# liron.net
KiCad netlist of a schematic drawn in EAGLE
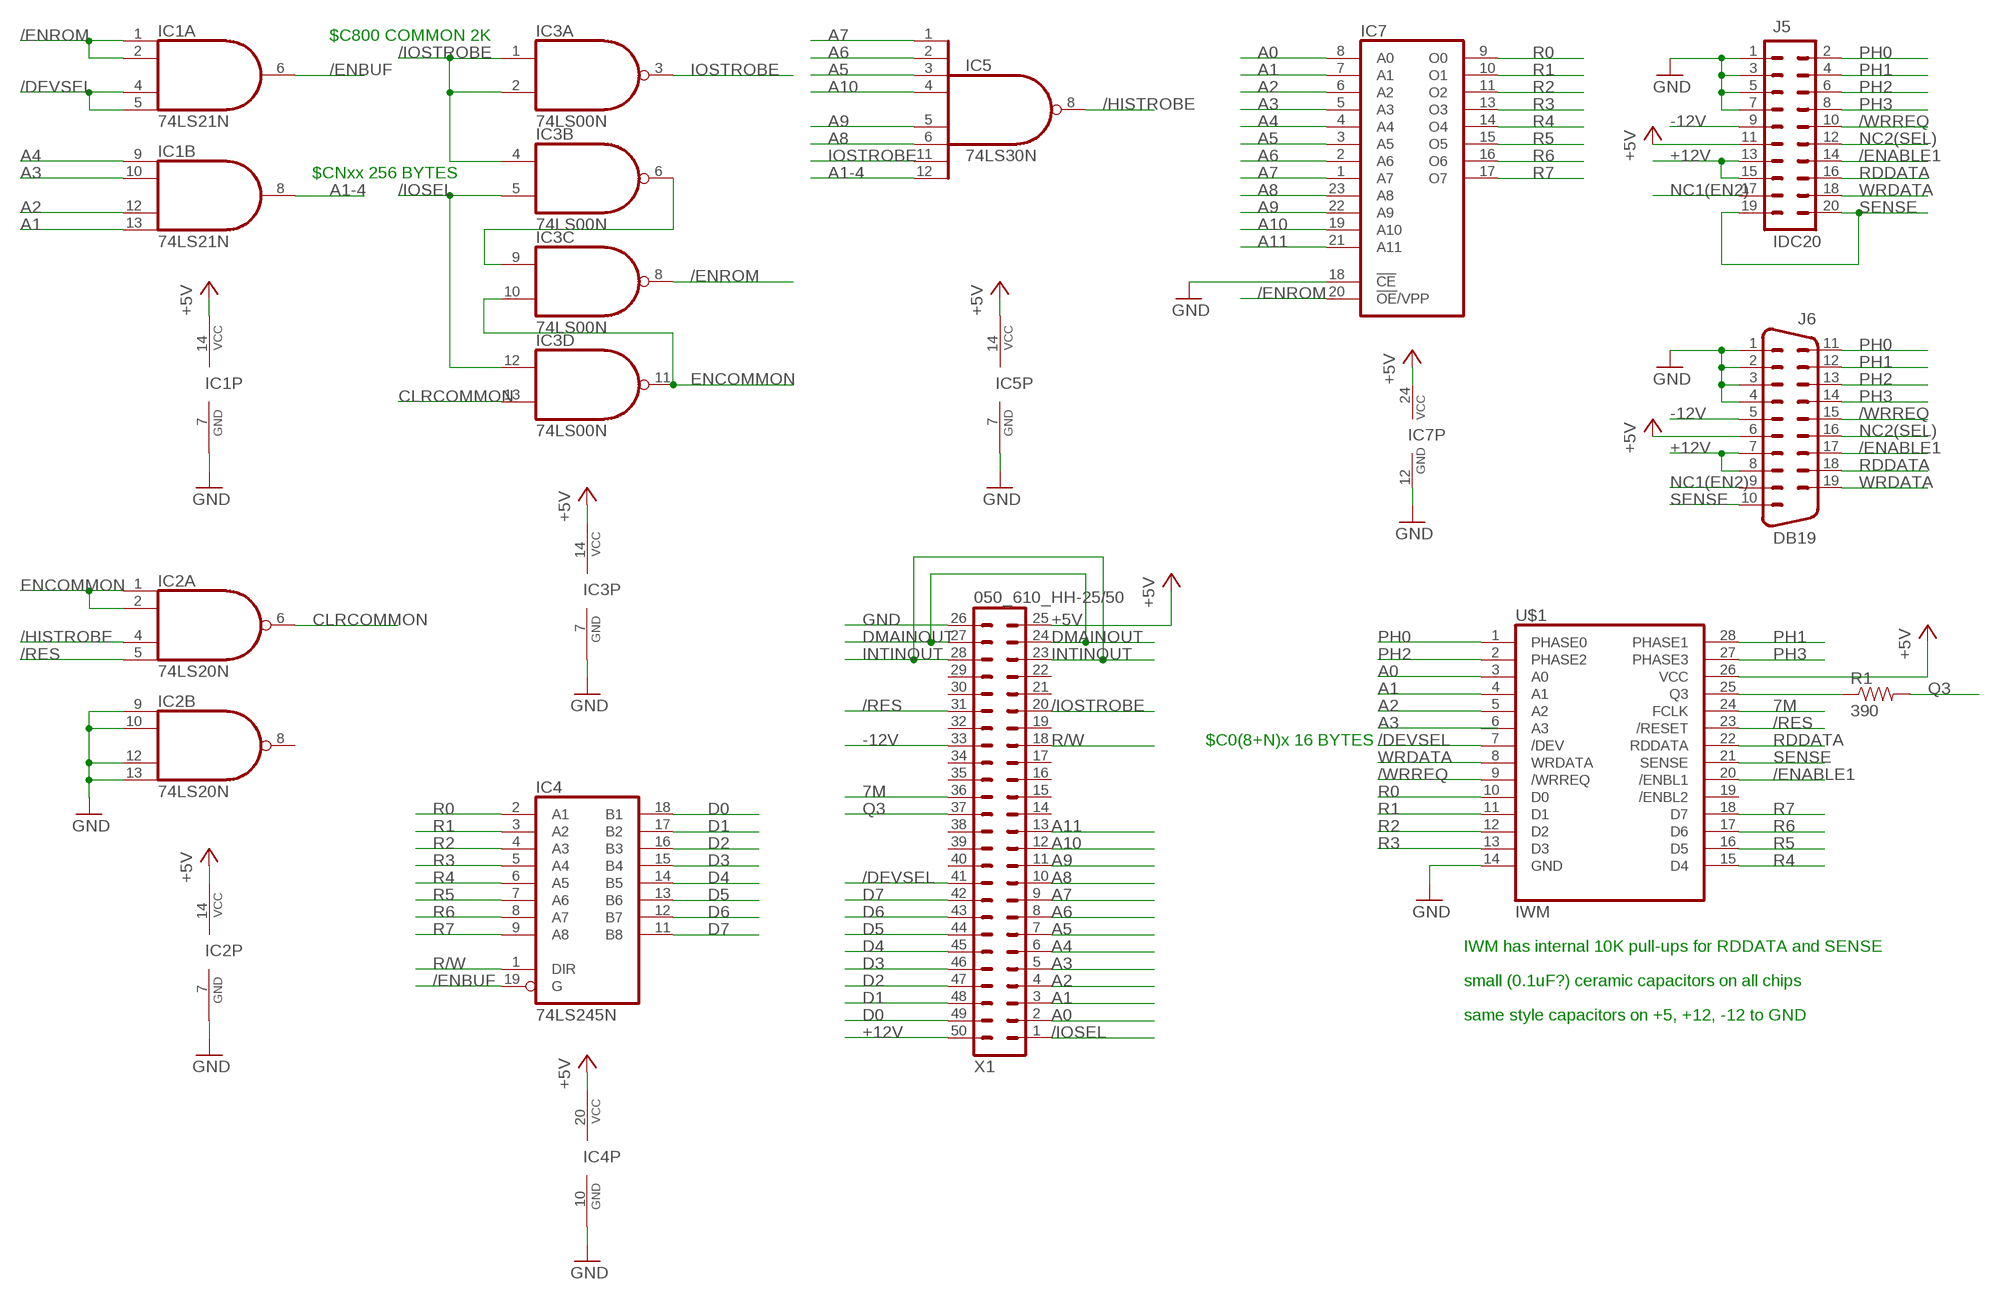
[diagram p0: schematic, sheet 1]

(export (version "E")
  (design (tool "Eeschema 10.0.6"))
  (components
    (comp (ref "IC1")
      (value "74LS21N")
      (footprint "eagle-import:DIL14")
      (libsource (lib "eagle-import") (part "7421NLS"))
    )
    (comp (ref "IC2")
      (value "74LS20N")
      (footprint "eagle-import:DIL14")
      (libsource (lib "eagle-import") (part "7420NLS"))
    )
    (comp (ref "IC3")
      (value "74LS00N")
      (footprint "eagle-import:DIL14")
      (libsource (lib "eagle-import") (part "7400NLS"))
    )
    (comp (ref "IC4")
      (value "74LS245N")
      (footprint "eagle-import:DIL20")
      (libsource (lib "eagle-import") (part "74245NLS"))
    )
    (comp (ref "IC5")
      (value "74LS30N")
      (footprint "eagle-import:DIL14")
      (libsource (lib "eagle-import") (part "7430NLS"))
    )
    (comp (ref "IC7")
      (value "2732")
      (footprint "eagle-import:DIL24")
      (libsource (lib "eagle-import") (part "2732"))
    )
    (comp (ref "J5")
      (value "IDC20")
      (footprint "eagle-import:IDC20")
      (libsource (lib "eagle-import") (part "IDC20"))
    )
    (comp (ref "J6")
      (value "DB19")
      (footprint "eagle-import:DB19EDGE")
      (libsource (lib "eagle-import") (part "DB19EDGE"))
    )
    (comp (ref "R1")
      (value "390")
      (footprint "eagle-import:0805")
      (libsource (lib "eagle-import") (part "RESISTOR0805-RES"))
    )
    (comp (ref "U$1")
      (value "IWM")
      (footprint "eagle-import:DIL28")
      (libsource (lib "eagle-import") (part "IWM"))
    )
    (comp (ref "X1")
      (value "050_610_HH-25/50")
      (footprint "eagle-import:050_610_HH-25_50")
      (libsource (lib "eagle-import") (part "050_610_?-25/50HH"))
    )
  )
  (nets
    (net (code "1") (name "+5V") (class "Default")
      (node (ref "IC1") (pin "14") (pinfunction "VCC_14") (pintype "power_in"))
      (node (ref "IC2") (pin "14") (pinfunction "VCC_14") (pintype "power_in"))
      (node (ref "IC3") (pin "14") (pinfunction "VCC_14") (pintype "power_in"))
      (node (ref "IC4") (pin "20") (pinfunction "VCC_20") (pintype "power_in"))
      (node (ref "IC5") (pin "14") (pinfunction "VCC_14") (pintype "power_in"))
      (node (ref "IC7") (pin "24") (pinfunction "VCC_24") (pintype "power_in"))
      (node (ref "J5") (pin "11") (pinfunction "11_11") (pintype "passive"))
      (node (ref "J6") (pin "6") (pinfunction "6_6") (pintype "passive"))
      (node (ref "U$1") (pin "26") (pinfunction "VCC_26") (pintype "tri_state"))
      (node (ref "X1") (pin "25") (pinfunction "25_25") (pintype "passive"))
    )
    (net (code "2") (name "/+12V") (class "Default")
      (node (ref "J5") (pin "13") (pinfunction "13_13") (pintype "passive"))
      (node (ref "J5") (pin "15") (pinfunction "15_15") (pintype "passive"))
      (node (ref "J6") (pin "7") (pinfunction "7_7") (pintype "passive"))
      (node (ref "J6") (pin "8") (pinfunction "8_8") (pintype "passive"))
      (node (ref "X1") (pin "50") (pinfunction "26_50") (pintype "passive"))
    )
    (net (code "3") (name "/-12V") (class "Default")
      (node (ref "J5") (pin "9") (pinfunction "9_9") (pintype "passive"))
      (node (ref "J6") (pin "5") (pinfunction "5_5") (pintype "passive"))
      (node (ref "X1") (pin "33") (pinfunction "43_33") (pintype "passive"))
    )
    (net (code "4") (name "/7M") (class "Default")
      (node (ref "U$1") (pin "24") (pinfunction "FCLK_24") (pintype "tri_state"))
      (node (ref "X1") (pin "36") (pinfunction "40_36") (pintype "passive"))
    )
    (net (code "5") (name "/A0") (class "Default")
      (node (ref "IC7") (pin "8") (pinfunction "A0_8") (pintype "input"))
      (node (ref "U$1") (pin "3") (pinfunction "A0_3") (pintype "input"))
      (node (ref "X1") (pin "2") (pinfunction "2_2") (pintype "passive"))
    )
    (net (code "6") (name "/A1") (class "Default")
      (node (ref "IC1") (pin "13") (pinfunction "I3_13") (pintype "input"))
      (node (ref "IC7") (pin "7") (pinfunction "A1_7") (pintype "input"))
      (node (ref "U$1") (pin "4") (pinfunction "A1_4") (pintype "input"))
      (node (ref "X1") (pin "3") (pinfunction "3_3") (pintype "passive"))
    )
    (net (code "7") (name "/A1-4") (class "Default")
      (node (ref "IC1") (pin "8") (pinfunction "O_8") (pintype "output"))
      (node (ref "IC5") (pin "12") (pinfunction "I7_12") (pintype "input"))
    )
    (net (code "8") (name "/A2") (class "Default")
      (node (ref "IC1") (pin "12") (pinfunction "I2_12") (pintype "input"))
      (node (ref "IC7") (pin "6") (pinfunction "A2_6") (pintype "input"))
      (node (ref "U$1") (pin "5") (pinfunction "A2_5") (pintype "input"))
      (node (ref "X1") (pin "4") (pinfunction "4_4") (pintype "passive"))
    )
    (net (code "9") (name "/A3") (class "Default")
      (node (ref "IC1") (pin "10") (pinfunction "I1_10") (pintype "input"))
      (node (ref "IC7") (pin "5") (pinfunction "A3_5") (pintype "input"))
      (node (ref "X1") (pin "5") (pinfunction "5_5") (pintype "passive"))
    )
    (net (code "10") (name "/A4") (class "Default")
      (node (ref "IC1") (pin "9") (pinfunction "I0_9") (pintype "input"))
      (node (ref "IC7") (pin "4") (pinfunction "A4_4") (pintype "input"))
      (node (ref "X1") (pin "6") (pinfunction "6_6") (pintype "passive"))
    )
    (net (code "11") (name "/A5") (class "Default")
      (node (ref "IC5") (pin "3") (pinfunction "I2_3") (pintype "input"))
      (node (ref "IC7") (pin "3") (pinfunction "A5_3") (pintype "input"))
      (node (ref "X1") (pin "7") (pinfunction "7_7") (pintype "passive"))
    )
    (net (code "12") (name "/A6") (class "Default")
      (node (ref "IC5") (pin "2") (pinfunction "I1_2") (pintype "input"))
      (node (ref "IC7") (pin "2") (pinfunction "A6_2") (pintype "input"))
      (node (ref "X1") (pin "8") (pinfunction "8_8") (pintype "passive"))
    )
    (net (code "13") (name "/A7") (class "Default")
      (node (ref "IC5") (pin "1") (pinfunction "I0_1") (pintype "input"))
      (node (ref "IC7") (pin "1") (pinfunction "A7_1") (pintype "input"))
      (node (ref "X1") (pin "9") (pinfunction "9_9") (pintype "passive"))
    )
    (net (code "14") (name "/A8") (class "Default")
      (node (ref "IC5") (pin "6") (pinfunction "I5_6") (pintype "input"))
      (node (ref "IC7") (pin "23") (pinfunction "A8_23") (pintype "input"))
      (node (ref "X1") (pin "10") (pinfunction "10_10") (pintype "passive"))
    )
    (net (code "15") (name "/A9") (class "Default")
      (node (ref "IC5") (pin "5") (pinfunction "I4_5") (pintype "input"))
      (node (ref "IC7") (pin "22") (pinfunction "A9_22") (pintype "input"))
      (node (ref "X1") (pin "11") (pinfunction "11_11") (pintype "passive"))
    )
    (net (code "16") (name "/A10") (class "Default")
      (node (ref "IC5") (pin "4") (pinfunction "I3_4") (pintype "input"))
      (node (ref "IC7") (pin "19") (pinfunction "A10_19") (pintype "input"))
      (node (ref "X1") (pin "12") (pinfunction "12_12") (pintype "passive"))
    )
    (net (code "17") (name "/A11") (class "Default")
      (node (ref "IC7") (pin "21") (pinfunction "A11_21") (pintype "input"))
      (node (ref "X1") (pin "13") (pinfunction "13_13") (pintype "passive"))
    )
    (net (code "18") (name "/CLRCOMMON") (class "Default")
      (node (ref "IC2") (pin "6") (pinfunction "O_6") (pintype "output"))
      (node (ref "IC3") (pin "13") (pinfunction "I1_13") (pintype "input"))
    )
    (net (code "19") (name "/D0") (class "Default")
      (node (ref "IC4") (pin "18") (pinfunction "B1_18") (pintype "bidirectional"))
      (node (ref "X1") (pin "49") (pinfunction "27_49") (pintype "passive"))
    )
    (net (code "20") (name "/D1") (class "Default")
      (node (ref "IC4") (pin "17") (pinfunction "B2_17") (pintype "bidirectional"))
      (node (ref "X1") (pin "48") (pinfunction "28_48") (pintype "passive"))
    )
    (net (code "21") (name "/D2") (class "Default")
      (node (ref "IC4") (pin "16") (pinfunction "B3_16") (pintype "bidirectional"))
      (node (ref "X1") (pin "47") (pinfunction "29_47") (pintype "passive"))
    )
    (net (code "22") (name "/D3") (class "Default")
      (node (ref "IC4") (pin "15") (pinfunction "B4_15") (pintype "bidirectional"))
      (node (ref "X1") (pin "46") (pinfunction "30_46") (pintype "passive"))
    )
    (net (code "23") (name "/D4") (class "Default")
      (node (ref "IC4") (pin "14") (pinfunction "B5_14") (pintype "bidirectional"))
      (node (ref "X1") (pin "45") (pinfunction "31_45") (pintype "passive"))
    )
    (net (code "24") (name "/D5") (class "Default")
      (node (ref "IC4") (pin "13") (pinfunction "B6_13") (pintype "bidirectional"))
      (node (ref "X1") (pin "44") (pinfunction "32_44") (pintype "passive"))
    )
    (net (code "25") (name "/D6") (class "Default")
      (node (ref "IC4") (pin "12") (pinfunction "B7_12") (pintype "bidirectional"))
      (node (ref "X1") (pin "43") (pinfunction "33_43") (pintype "passive"))
    )
    (net (code "26") (name "/D7") (class "Default")
      (node (ref "IC4") (pin "11") (pinfunction "B8_11") (pintype "bidirectional"))
      (node (ref "X1") (pin "42") (pinfunction "34_42") (pintype "passive"))
    )
    (net (code "27") (name "/DMAINOUT") (class "Default")
      (node (ref "X1") (pin "24") (pinfunction "24_24") (pintype "passive"))
      (node (ref "X1") (pin "27") (pinfunction "49_27") (pintype "passive"))
    )
    (net (code "28") (name "/ENCOMMON") (class "Default")
      (node (ref "IC2") (pin "1") (pinfunction "I0_1") (pintype "input"))
      (node (ref "IC2") (pin "2") (pinfunction "I1_2") (pintype "input"))
      (node (ref "IC3") (pin "10") (pinfunction "I1_10") (pintype "input"))
      (node (ref "IC3") (pin "11") (pinfunction "O_11") (pintype "output"))
    )
    (net (code "29") (name "/INTINOUT") (class "Default")
      (node (ref "X1") (pin "23") (pinfunction "23_23") (pintype "passive"))
      (node (ref "X1") (pin "28") (pinfunction "48_28") (pintype "passive"))
    )
    (net (code "30") (name "/IOSTROBE") (class "Default")
      (node (ref "IC3") (pin "3") (pinfunction "O_3") (pintype "output"))
      (node (ref "IC5") (pin "11") (pinfunction "I6_11") (pintype "input"))
    )
    (net (code "31") (name "/NC1(EN2)") (class "Default")
      (node (ref "J5") (pin "17") (pinfunction "17_17") (pintype "passive"))
      (node (ref "J6") (pin "9") (pinfunction "9_9") (pintype "passive"))
    )
    (net (code "32") (name "/NC2(SEL)") (class "Default")
      (node (ref "J5") (pin "12") (pinfunction "12_12") (pintype "passive"))
      (node (ref "J6") (pin "16") (pinfunction "16_16") (pintype "passive"))
    )
    (net (code "33") (name "/PH0") (class "Default")
      (node (ref "J5") (pin "2") (pinfunction "2_2") (pintype "passive"))
      (node (ref "J6") (pin "11") (pinfunction "11_11") (pintype "passive"))
      (node (ref "U$1") (pin "1") (pinfunction "PHASE0_1") (pintype "input"))
    )
    (net (code "34") (name "/PH1") (class "Default")
      (node (ref "J5") (pin "4") (pinfunction "4_4") (pintype "passive"))
      (node (ref "J6") (pin "12") (pinfunction "12_12") (pintype "passive"))
      (node (ref "U$1") (pin "28") (pinfunction "PHASE1_28") (pintype "tri_state"))
    )
    (net (code "35") (name "/PH2") (class "Default")
      (node (ref "J5") (pin "6") (pinfunction "6_6") (pintype "passive"))
      (node (ref "J6") (pin "13") (pinfunction "13_13") (pintype "passive"))
      (node (ref "U$1") (pin "2") (pinfunction "PHASE2_2") (pintype "input"))
    )
    (net (code "36") (name "/PH3") (class "Default")
      (node (ref "J5") (pin "8") (pinfunction "8_8") (pintype "passive"))
      (node (ref "J6") (pin "14") (pinfunction "14_14") (pintype "passive"))
      (node (ref "U$1") (pin "27") (pinfunction "PHASE3_27") (pintype "tri_state"))
    )
    (net (code "37") (name "/Q3") (class "Default")
      (node (ref "R1") (pin "2") (pinfunction "2_2") (pintype "passive"))
      (node (ref "X1") (pin "37") (pinfunction "39_37") (pintype "passive"))
    )
    (net (code "38") (name "/R0") (class "Default")
      (node (ref "IC4") (pin "2") (pinfunction "A1_2") (pintype "bidirectional"))
      (node (ref "IC7") (pin "9") (pinfunction "O0_9") (pintype "tri_state"))
      (node (ref "U$1") (pin "10") (pinfunction "D0_10") (pintype "input"))
    )
    (net (code "39") (name "/R1") (class "Default")
      (node (ref "IC4") (pin "3") (pinfunction "A2_3") (pintype "bidirectional"))
      (node (ref "IC7") (pin "10") (pinfunction "O1_10") (pintype "tri_state"))
      (node (ref "U$1") (pin "11") (pinfunction "D1_11") (pintype "input"))
    )
    (net (code "40") (name "/R2") (class "Default")
      (node (ref "IC4") (pin "4") (pinfunction "A3_4") (pintype "bidirectional"))
      (node (ref "IC7") (pin "11") (pinfunction "O2_11") (pintype "tri_state"))
      (node (ref "U$1") (pin "12") (pinfunction "D2_12") (pintype "input"))
    )
    (net (code "41") (name "/R3") (class "Default")
      (node (ref "IC4") (pin "5") (pinfunction "A4_5") (pintype "bidirectional"))
      (node (ref "IC7") (pin "13") (pinfunction "O3_13") (pintype "tri_state"))
      (node (ref "U$1") (pin "13") (pinfunction "D3_13") (pintype "input"))
    )
    (net (code "42") (name "/R4") (class "Default")
      (node (ref "IC4") (pin "6") (pinfunction "A5_6") (pintype "bidirectional"))
      (node (ref "IC7") (pin "14") (pinfunction "O4_14") (pintype "tri_state"))
      (node (ref "U$1") (pin "15") (pinfunction "D4_15") (pintype "tri_state"))
    )
    (net (code "43") (name "/R5") (class "Default")
      (node (ref "IC4") (pin "7") (pinfunction "A6_7") (pintype "bidirectional"))
      (node (ref "IC7") (pin "15") (pinfunction "O5_15") (pintype "tri_state"))
      (node (ref "U$1") (pin "16") (pinfunction "D5_16") (pintype "tri_state"))
    )
    (net (code "44") (name "/R6") (class "Default")
      (node (ref "IC4") (pin "8") (pinfunction "A7_8") (pintype "bidirectional"))
      (node (ref "IC7") (pin "16") (pinfunction "O6_16") (pintype "tri_state"))
      (node (ref "U$1") (pin "17") (pinfunction "D6_17") (pintype "tri_state"))
    )
    (net (code "45") (name "/R7") (class "Default")
      (node (ref "IC4") (pin "9") (pinfunction "A8_9") (pintype "bidirectional"))
      (node (ref "IC7") (pin "17") (pinfunction "O7_17") (pintype "tri_state"))
      (node (ref "U$1") (pin "18") (pinfunction "D7_18") (pintype "tri_state"))
    )
    (net (code "46") (name "/RDDATA") (class "Default")
      (node (ref "J5") (pin "16") (pinfunction "16_16") (pintype "passive"))
      (node (ref "J6") (pin "18") (pinfunction "18_18") (pintype "passive"))
      (node (ref "U$1") (pin "22") (pinfunction "RDDATA_22") (pintype "tri_state"))
    )
    (net (code "47") (name "/R{slash}W") (class "Default")
      (node (ref "IC4") (pin "1") (pinfunction "DIR_1") (pintype "input"))
      (node (ref "X1") (pin "18") (pinfunction "18_18") (pintype "passive"))
    )
    (net (code "48") (name "/SENSE") (class "Default")
      (node (ref "J5") (pin "19") (pinfunction "19_19") (pintype "passive"))
      (node (ref "J5") (pin "20") (pinfunction "20_20") (pintype "passive"))
      (node (ref "J6") (pin "10") (pinfunction "10_10") (pintype "passive"))
      (node (ref "U$1") (pin "21") (pinfunction "SENSE_21") (pintype "tri_state"))
    )
    (net (code "49") (name "/WRDATA") (class "Default")
      (node (ref "J5") (pin "18") (pinfunction "18_18") (pintype "passive"))
      (node (ref "J6") (pin "19") (pinfunction "19_19") (pintype "passive"))
      (node (ref "U$1") (pin "8") (pinfunction "WRDATA_8") (pintype "input"))
    )
    (net (code "50") (name "/{slash}DEVSEL") (class "Default")
      (node (ref "IC1") (pin "4") (pinfunction "I2_4") (pintype "input"))
      (node (ref "IC1") (pin "5") (pinfunction "I3_5") (pintype "input"))
      (node (ref "U$1") (pin "7") (pinfunction "/DEV_7") (pintype "input"))
      (node (ref "X1") (pin "41") (pinfunction "35_41") (pintype "passive"))
    )
    (net (code "51") (name "/{slash}ENABLE1") (class "Default")
      (node (ref "J5") (pin "14") (pinfunction "14_14") (pintype "passive"))
      (node (ref "J6") (pin "17") (pinfunction "17_17") (pintype "passive"))
      (node (ref "U$1") (pin "20") (pinfunction "/ENBL1_20") (pintype "tri_state"))
    )
    (net (code "52") (name "/{slash}ENBUF") (class "Default")
      (node (ref "IC1") (pin "6") (pinfunction "O_6") (pintype "output"))
      (node (ref "IC4") (pin "19") (pinfunction "G_19") (pintype "input"))
    )
    (net (code "53") (name "/{slash}ENROM") (class "Default")
      (node (ref "IC1") (pin "1") (pinfunction "I0_1") (pintype "input"))
      (node (ref "IC1") (pin "2") (pinfunction "I1_2") (pintype "input"))
      (node (ref "IC3") (pin "8") (pinfunction "O_8") (pintype "output"))
      (node (ref "IC7") (pin "20") (pinfunction "~{OE}/VPP_20") (pintype "input"))
    )
    (net (code "54") (name "/{slash}HISTROBE") (class "Default")
      (node (ref "IC2") (pin "4") (pinfunction "I2_4") (pintype "input"))
      (node (ref "IC5") (pin "8") (pinfunction "O_8") (pintype "output"))
    )
    (net (code "55") (name "/{slash}IOSEL") (class "Default")
      (node (ref "IC3") (pin "12") (pinfunction "I0_12") (pintype "input"))
      (node (ref "IC3") (pin "5") (pinfunction "I1_5") (pintype "input"))
      (node (ref "X1") (pin "1") (pinfunction "1_1") (pintype "passive"))
    )
    (net (code "56") (name "/{slash}IOSTROBE") (class "Default")
      (node (ref "IC3") (pin "1") (pinfunction "I0_1") (pintype "input"))
      (node (ref "IC3") (pin "2") (pinfunction "I1_2") (pintype "input"))
      (node (ref "IC3") (pin "4") (pinfunction "I0_4") (pintype "input"))
      (node (ref "X1") (pin "20") (pinfunction "20_20") (pintype "passive"))
    )
    (net (code "57") (name "/{slash}RES") (class "Default")
      (node (ref "IC2") (pin "5") (pinfunction "I3_5") (pintype "input"))
      (node (ref "U$1") (pin "23") (pinfunction "/RESET_23") (pintype "tri_state"))
      (node (ref "X1") (pin "31") (pinfunction "45_31") (pintype "passive"))
    )
    (net (code "58") (name "/{slash}WRREQ") (class "Default")
      (node (ref "J5") (pin "10") (pinfunction "10_10") (pintype "passive"))
      (node (ref "J6") (pin "15") (pinfunction "15_15") (pintype "passive"))
      (node (ref "U$1") (pin "9") (pinfunction "/WRREQ_9") (pintype "input"))
    )
    (net (code "59") (name "GND") (class "Default")
      (node (ref "IC1") (pin "7") (pinfunction "GND_7") (pintype "power_in"))
      (node (ref "IC2") (pin "10") (pinfunction "I1_10") (pintype "input"))
      (node (ref "IC2") (pin "12") (pinfunction "I2_12") (pintype "input"))
      (node (ref "IC2") (pin "13") (pinfunction "I3_13") (pintype "input"))
      (node (ref "IC2") (pin "7") (pinfunction "GND_7") (pintype "power_in"))
      (node (ref "IC2") (pin "9") (pinfunction "I0_9") (pintype "input"))
      (node (ref "IC3") (pin "7") (pinfunction "GND_7") (pintype "power_in"))
      (node (ref "IC4") (pin "10") (pinfunction "GND_10") (pintype "power_in"))
      (node (ref "IC5") (pin "7") (pinfunction "GND_7") (pintype "power_in"))
      (node (ref "IC7") (pin "12") (pinfunction "GND_12") (pintype "power_in"))
      (node (ref "IC7") (pin "18") (pinfunction "~{CE}_18") (pintype "input"))
      (node (ref "J5") (pin "1") (pinfunction "1_1") (pintype "passive"))
      (node (ref "J5") (pin "3") (pinfunction "3_3") (pintype "passive"))
      (node (ref "J5") (pin "5") (pinfunction "5_5") (pintype "passive"))
      (node (ref "J5") (pin "7") (pinfunction "7_7") (pintype "passive"))
      (node (ref "J6") (pin "1") (pinfunction "1_1") (pintype "passive"))
      (node (ref "J6") (pin "2") (pinfunction "2_2") (pintype "passive"))
      (node (ref "J6") (pin "3") (pinfunction "3_3") (pintype "passive"))
      (node (ref "J6") (pin "4") (pinfunction "4_4") (pintype "passive"))
      (node (ref "U$1") (pin "14") (pinfunction "GND_14") (pintype "input"))
      (node (ref "X1") (pin "26") (pinfunction "50_26") (pintype "passive"))
    )
    (net (code "60") (name "Net-(IC3B-O)") (class "Default")
      (node (ref "IC3") (pin "6") (pinfunction "O_6") (pintype "output"))
      (node (ref "IC3") (pin "9") (pinfunction "I0_9") (pintype "input"))
    )
    (net (code "61") (name "Net-(U$1-Q3)") (class "Default")
      (node (ref "R1") (pin "1") (pinfunction "1_1") (pintype "passive"))
      (node (ref "U$1") (pin "25") (pinfunction "Q3_25") (pintype "tri_state"))
    )
    (net (code "62") (name "unconnected-(IC2B-O-Pad8)") (class "Default")
      (node (ref "IC2") (pin "8") (pinfunction "O_8") (pintype "output"))
    )
    (net (code "63") (name "unconnected-(U$1-A3-Pad6)") (class "Default")
      (node (ref "U$1") (pin "6") (pinfunction "A3_6") (pintype "input"))
    )
    (net (code "64") (name "unconnected-(U$1-{slash}ENBL2-Pad19)") (class "Default")
      (node (ref "U$1") (pin "19") (pinfunction "/ENBL2_19") (pintype "tri_state"))
    )
    (net (code "65") (name "unconnected-(X1-36-Pad40)") (class "Default")
      (node (ref "X1") (pin "40") (pinfunction "36_40") (pintype "passive"))
    )
    (net (code "66") (name "unconnected-(X1-37-Pad39)") (class "Default")
      (node (ref "X1") (pin "39") (pinfunction "37_39") (pintype "passive"))
    )
    (net (code "67") (name "unconnected-(X1-41-Pad35)") (class "Default")
      (node (ref "X1") (pin "35") (pinfunction "41_35") (pintype "passive"))
    )
    (net (code "68") (name "unconnected-(X1-42-Pad34)") (class "Default")
      (node (ref "X1") (pin "34") (pinfunction "42_34") (pintype "passive"))
    )
    (net (code "69") (name "unconnected-(X1-44-Pad32)") (class "Default")
      (node (ref "X1") (pin "32") (pinfunction "44_32") (pintype "passive"))
    )
    (net (code "70") (name "unconnected-(X1-46-Pad30)") (class "Default")
      (node (ref "X1") (pin "30") (pinfunction "46_30") (pintype "passive"))
    )
    (net (code "71") (name "unconnected-(X1-47-Pad29)") (class "Default")
      (node (ref "X1") (pin "29") (pinfunction "47_29") (pintype "passive"))
    )
    (net (code "72") (name "unconnected-(X1-Pad14)") (class "Default")
      (node (ref "X1") (pin "14") (pinfunction "14_14") (pintype "passive"))
    )
    (net (code "73") (name "unconnected-(X1-Pad15)") (class "Default")
      (node (ref "X1") (pin "15") (pinfunction "15_15") (pintype "passive"))
    )
    (net (code "74") (name "unconnected-(X1-Pad16)") (class "Default")
      (node (ref "X1") (pin "16") (pinfunction "16_16") (pintype "passive"))
    )
    (net (code "75") (name "unconnected-(X1-Pad17)") (class "Default")
      (node (ref "X1") (pin "17") (pinfunction "17_17") (pintype "passive"))
    )
    (net (code "76") (name "unconnected-(X1-Pad19)") (class "Default")
      (node (ref "X1") (pin "19") (pinfunction "19_19") (pintype "passive"))
    )
    (net (code "77") (name "unconnected-(X1-Pad21)") (class "Default")
      (node (ref "X1") (pin "21") (pinfunction "21_21") (pintype "passive"))
    )
    (net (code "78") (name "unconnected-(X1-Pad22)") (class "Default")
      (node (ref "X1") (pin "22") (pinfunction "22_22") (pintype "passive"))
    )
    (net (code "79") (name "unconnected-(X1-Pad38)") (class "Default")
      (node (ref "X1") (pin "38") (pinfunction "38_38") (pintype "passive"))
    )
  )
)
